# pc_max30003_brk_v2_0.net
KiCad netlist of a schematic drawn in EAGLE
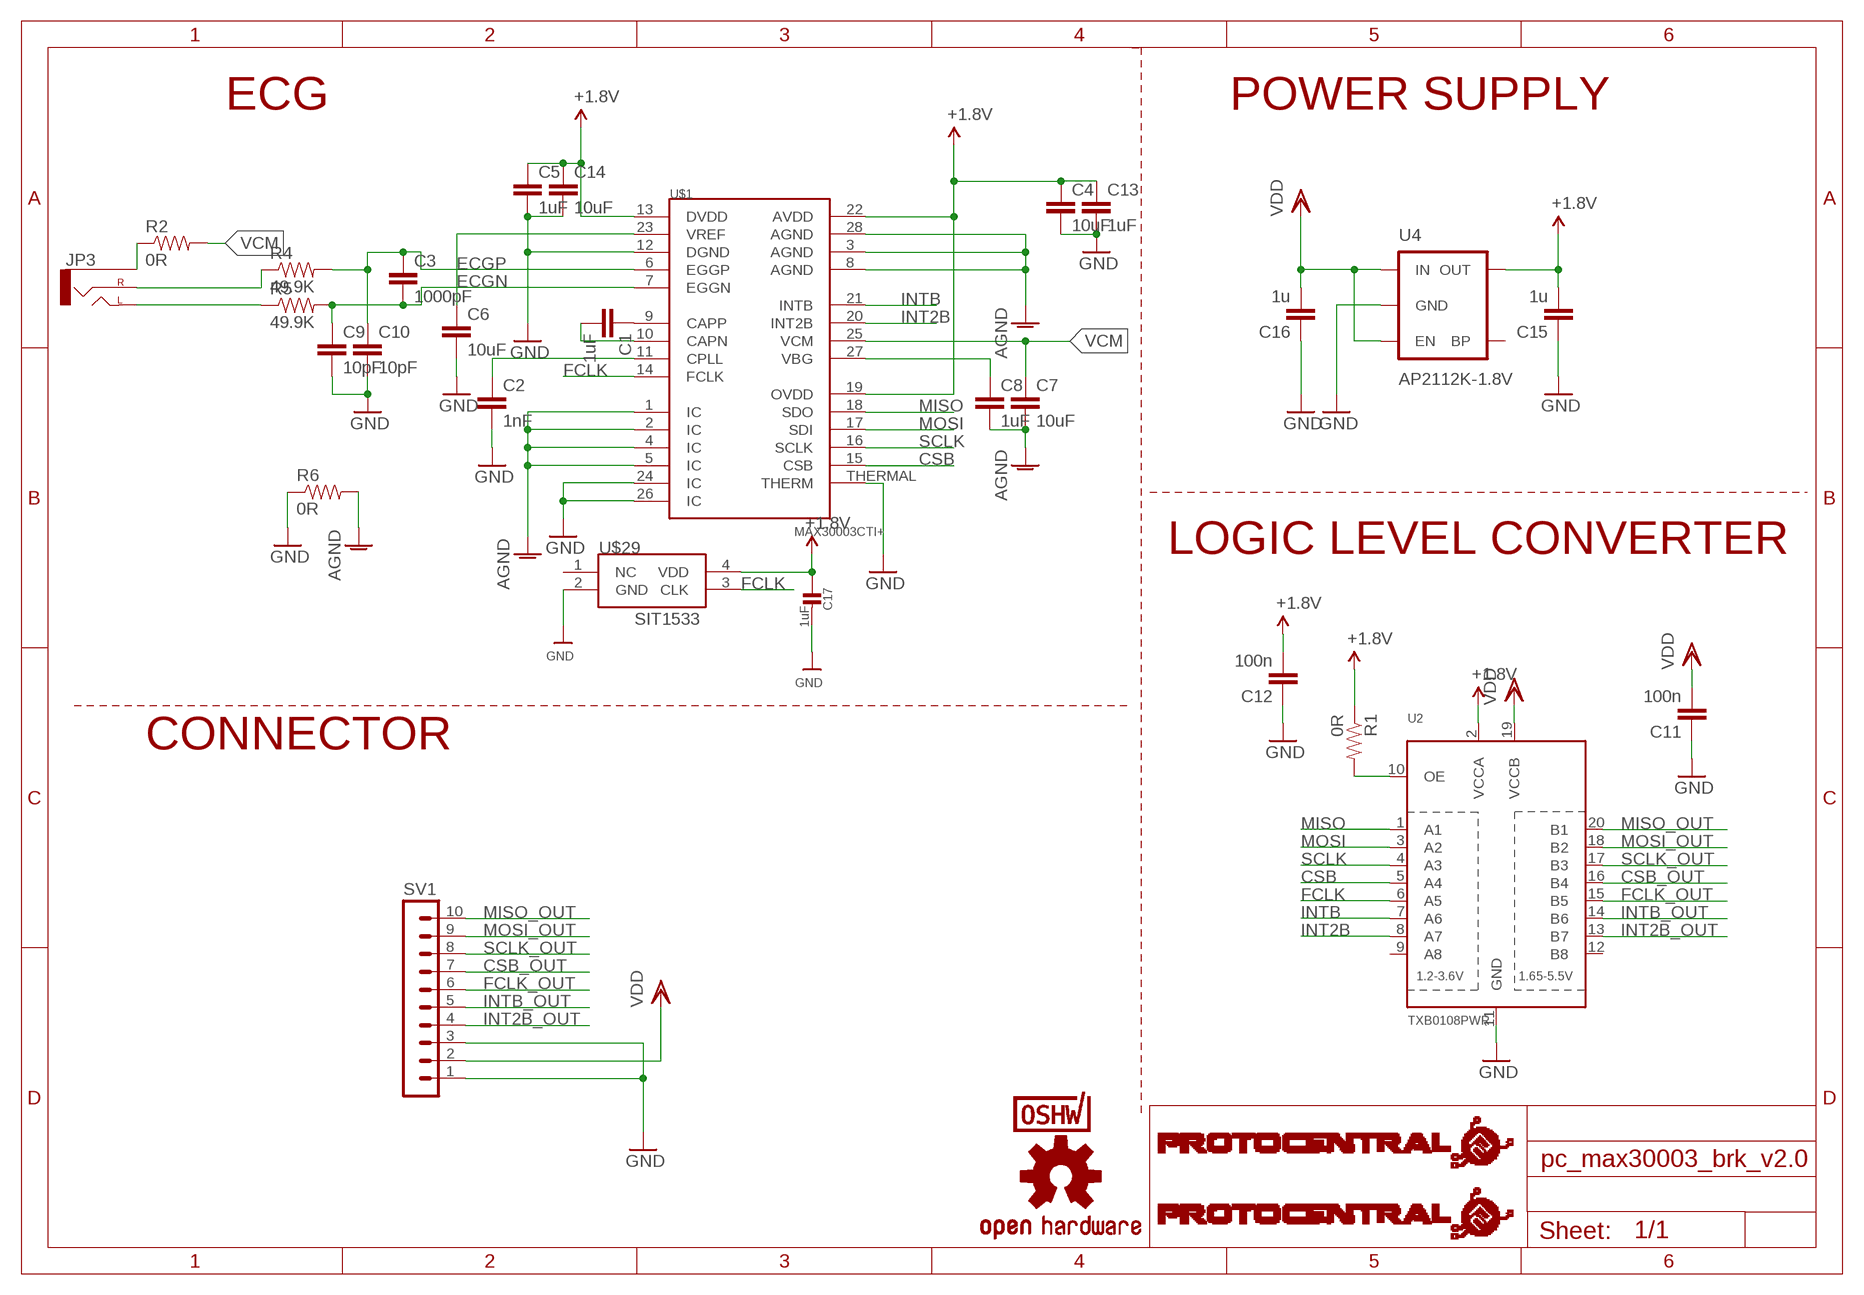
[diagram p0: schematic, sheet 1]

(export (version "E")
  (design (tool "Eeschema 10.0.6"))
  (components
    (comp (ref "C1")
      (value "1uF")
      (footprint "eagle-import:C0805")
      (libsource (lib "eagle-import") (part "C-EUC0805"))
    )
    (comp (ref "C2")
      (value "1nF")
      (footprint "eagle-import:C0805")
      (libsource (lib "eagle-import") (part "C-EUC0805"))
    )
    (comp (ref "C3")
      (value "1000pF")
      (footprint "eagle-import:C0402")
      (libsource (lib "eagle-import") (part "C-EUC0402"))
    )
    (comp (ref "C4")
      (value "10uF")
      (footprint "eagle-import:C0805")
      (libsource (lib "eagle-import") (part "C-EUC0805"))
    )
    (comp (ref "C5")
      (value "1uF")
      (footprint "eagle-import:C0805")
      (libsource (lib "eagle-import") (part "C-EUC0805"))
    )
    (comp (ref "C6")
      (value "10uF")
      (footprint "eagle-import:C0805")
      (libsource (lib "eagle-import") (part "C-EUC0805"))
    )
    (comp (ref "C7")
      (value "10uF")
      (footprint "eagle-import:C0805")
      (libsource (lib "eagle-import") (part "C-EUC0805"))
    )
    (comp (ref "C8")
      (value "1uF")
      (footprint "eagle-import:C0805")
      (libsource (lib "eagle-import") (part "C-EUC0805"))
    )
    (comp (ref "C9")
      (value "10pF")
      (footprint "eagle-import:C0402")
      (libsource (lib "eagle-import") (part "C-EUC0402"))
    )
    (comp (ref "C10")
      (value "10pF")
      (footprint "eagle-import:C0402")
      (libsource (lib "eagle-import") (part "C-EUC0402"))
    )
    (comp (ref "C11")
      (value "100n")
      (footprint "eagle-import:C0402")
      (libsource (lib "eagle-import") (part "C-EUC0402"))
    )
    (comp (ref "C12")
      (value "100n")
      (footprint "eagle-import:C0402")
      (libsource (lib "eagle-import") (part "C-EUC0402"))
    )
    (comp (ref "C13")
      (value "1uF")
      (footprint "eagle-import:C0805")
      (libsource (lib "eagle-import") (part "C-EUC0805"))
    )
    (comp (ref "C14")
      (value "10uF")
      (footprint "eagle-import:C0805")
      (libsource (lib "eagle-import") (part "C-EUC0805"))
    )
    (comp (ref "C15")
      (value "1u")
      (footprint "eagle-import:C0805")
      (libsource (lib "eagle-import") (part "C-EUC0805"))
    )
    (comp (ref "C16")
      (value "1u")
      (footprint "eagle-import:C0805")
      (libsource (lib "eagle-import") (part "C-EUC0805"))
    )
    (comp (ref "C17")
      (value "1uF")
      (footprint "eagle-import:_0402")
      (libsource (lib "eagle-import") (part "CAP_CERAMIC_0402"))
    )
    (comp (ref "JP3")
      (value "AUDIO-JACKSMD2")
      (footprint "eagle-import:AUDIO-JACK-3.5MM-SMD")
      (libsource (lib "eagle-import") (part "AUDIO-JACKSMD2"))
    )
    (comp (ref "R1")
      (value "0R")
      (footprint "eagle-import:0805")
      (libsource (lib "eagle-import") (part "RESISTOR0805-RES"))
    )
    (comp (ref "R2")
      (value "0R")
      (footprint "eagle-import:0805")
      (libsource (lib "eagle-import") (part "RESISTOR0805-RES"))
    )
    (comp (ref "R4")
      (value "49.9K")
      (footprint "eagle-import:0805")
      (libsource (lib "eagle-import") (part "RESISTOR0805-RES"))
    )
    (comp (ref "R5")
      (value "49.9K")
      (footprint "eagle-import:0805")
      (libsource (lib "eagle-import") (part "RESISTOR0805-RES"))
    )
    (comp (ref "R6")
      (value "0R")
      (footprint "eagle-import:0805")
      (libsource (lib "eagle-import") (part "RESISTOR0805-RES"))
    )
    (comp (ref "SV1")
      (value "MA10-1")
      (footprint "eagle-import:MA10-1")
      (libsource (lib "eagle-import") (part "MA10-1"))
    )
    (comp (ref "U$1")
      (value "MAX30003CTI+")
      (footprint "eagle-import:QFN-28")
      (libsource (lib "eagle-import") (part "MAX30003"))
    )
    (comp (ref "U$2")
      (value "PROTY_LOGO_WITH_TEXT")
      (footprint "eagle-import:PROTY_WITH_TEXT")
      (libsource (lib "eagle-import") (part "PROTY_LOGO_WITH_TEXT"))
    )
    (comp (ref "U$3")
      (value "PROTY-LOGO")
      (footprint "eagle-import:LOGO-PROTY")
      (libsource (lib "eagle-import") (part "PROTY-LOGO"))
    )
    (comp (ref "U$6")
      (value "OSHW-LOGOS")
      (footprint "eagle-import:OSHW-LOGO-S")
      (libsource (lib "eagle-import") (part "OSHW-LOGOS"))
    )
    (comp (ref "U$7")
      (value "CERT-SMALL")
      (footprint "eagle-import:CERT-SMALL-SILK")
      (libsource (lib "eagle-import") (part "CERT-SMALL"))
    )
    (comp (ref "U$29")
      (value "SIT1533")
      (footprint "eagle-import:SIT1533")
      (libsource (lib "eagle-import") (part "SIT1533"))
    )
    (comp (ref "U2")
      (value "TXB0108PWR")
      (footprint "eagle-import:TSSOP20")
      (libsource (lib "eagle-import") (part "TXB0108PWR"))
    )
    (comp (ref "U4")
      (value "AP2112K-1.8V")
      (footprint "eagle-import:SOT23-5")
      (libsource (lib "eagle-import") (part "V_REG_LDOSMD"))
    )
  )
  (nets
    (net (code "1") (name "+1.8V") (class "Default")
      (node (ref "C12") (pin "2") (pinfunction "2_2") (pintype "passive"))
      (node (ref "C13") (pin "1") (pinfunction "1_1") (pintype "passive"))
      (node (ref "C14") (pin "1") (pinfunction "1_1") (pintype "passive"))
      (node (ref "C15") (pin "2") (pinfunction "2_2") (pintype "passive"))
      (node (ref "C17") (pin "1") (pinfunction "1_1") (pintype "passive"))
      (node (ref "C4") (pin "1") (pinfunction "1_1") (pintype "passive"))
      (node (ref "C5") (pin "1") (pinfunction "1_1") (pintype "passive"))
      (node (ref "R1") (pin "1") (pinfunction "1_1") (pintype "passive"))
      (node (ref "U$1") (pin "13") (pinfunction "DVDD_13") (pintype "bidirectional"))
      (node (ref "U$1") (pin "19") (pinfunction "OVDD_19") (pintype "bidirectional"))
      (node (ref "U$1") (pin "22") (pinfunction "AVDD_22") (pintype "bidirectional"))
      (node (ref "U$29") (pin "4") (pinfunction "VDD_4") (pintype "bidirectional"))
      (node (ref "U2") (pin "2") (pinfunction "VCCA_2") (pintype "bidirectional"))
      (node (ref "U4") (pin "5") (pinfunction "OUT_5") (pintype "passive"))
    )
    (net (code "2") (name "/CSB") (class "Default")
      (node (ref "U$1") (pin "15") (pinfunction "CSB_15") (pintype "bidirectional"))
      (node (ref "U2") (pin "5") (pinfunction "A4_5") (pintype "bidirectional"))
    )
    (net (code "3") (name "/CSB_OUT") (class "Default")
      (node (ref "SV1") (pin "7") (pinfunction "7_7") (pintype "passive"))
      (node (ref "U2") (pin "16") (pinfunction "B4_16") (pintype "bidirectional"))
    )
    (net (code "4") (name "/ECGN") (class "Default")
      (node (ref "C3") (pin "2") (pinfunction "2_2") (pintype "passive"))
      (node (ref "C9") (pin "1") (pinfunction "1_1") (pintype "passive"))
      (node (ref "R5") (pin "2") (pinfunction "2_2") (pintype "passive"))
      (node (ref "U$1") (pin "7") (pinfunction "EGGN_7") (pintype "bidirectional"))
    )
    (net (code "5") (name "/ECGP") (class "Default")
      (node (ref "C10") (pin "1") (pinfunction "1_1") (pintype "passive"))
      (node (ref "C3") (pin "1") (pinfunction "1_1") (pintype "passive"))
      (node (ref "R4") (pin "2") (pinfunction "2_2") (pintype "passive"))
      (node (ref "U$1") (pin "6") (pinfunction "EGGP_6") (pintype "bidirectional"))
    )
    (net (code "6") (name "/FCLK") (class "Default")
      (node (ref "U$1") (pin "14") (pinfunction "FCLK_14") (pintype "bidirectional"))
      (node (ref "U$29") (pin "3") (pinfunction "CLK_3") (pintype "bidirectional"))
      (node (ref "U2") (pin "6") (pinfunction "A5_6") (pintype "bidirectional"))
    )
    (net (code "7") (name "/FCLK_OUT") (class "Default")
      (node (ref "SV1") (pin "6") (pinfunction "6_6") (pintype "passive"))
      (node (ref "U2") (pin "15") (pinfunction "B5_15") (pintype "bidirectional"))
    )
    (net (code "8") (name "/INT2B") (class "Default")
      (node (ref "U$1") (pin "20") (pinfunction "INT2B_20") (pintype "bidirectional"))
      (node (ref "U2") (pin "8") (pinfunction "A7_8") (pintype "bidirectional"))
    )
    (net (code "9") (name "/INT2B_OUT") (class "Default")
      (node (ref "SV1") (pin "4") (pinfunction "4_4") (pintype "passive"))
      (node (ref "U2") (pin "13") (pinfunction "B7_13") (pintype "bidirectional"))
    )
    (net (code "10") (name "/INTB") (class "Default")
      (node (ref "U$1") (pin "21") (pinfunction "INTB_21") (pintype "bidirectional"))
      (node (ref "U2") (pin "7") (pinfunction "A6_7") (pintype "bidirectional"))
    )
    (net (code "11") (name "/INTB_OUT") (class "Default")
      (node (ref "SV1") (pin "5") (pinfunction "5_5") (pintype "passive"))
      (node (ref "U2") (pin "14") (pinfunction "B6_14") (pintype "bidirectional"))
    )
    (net (code "12") (name "/MISO") (class "Default")
      (node (ref "U$1") (pin "18") (pinfunction "SDO_18") (pintype "bidirectional"))
      (node (ref "U2") (pin "1") (pinfunction "A1_1") (pintype "bidirectional"))
    )
    (net (code "13") (name "/MISO_OUT") (class "Default")
      (node (ref "SV1") (pin "10") (pinfunction "10_10") (pintype "passive"))
      (node (ref "U2") (pin "20") (pinfunction "B1_20") (pintype "bidirectional"))
    )
    (net (code "14") (name "/MOSI") (class "Default")
      (node (ref "U$1") (pin "17") (pinfunction "SDI_17") (pintype "bidirectional"))
      (node (ref "U2") (pin "3") (pinfunction "A2_3") (pintype "bidirectional"))
    )
    (net (code "15") (name "/MOSI_OUT") (class "Default")
      (node (ref "SV1") (pin "9") (pinfunction "9_9") (pintype "passive"))
      (node (ref "U2") (pin "18") (pinfunction "B2_18") (pintype "bidirectional"))
    )
    (net (code "16") (name "/SCLK") (class "Default")
      (node (ref "U$1") (pin "16") (pinfunction "SCLK_16") (pintype "bidirectional"))
      (node (ref "U2") (pin "4") (pinfunction "A3_4") (pintype "bidirectional"))
    )
    (net (code "17") (name "/SCLK_OUT") (class "Default")
      (node (ref "SV1") (pin "8") (pinfunction "8_8") (pintype "passive"))
      (node (ref "U2") (pin "17") (pinfunction "B3_17") (pintype "bidirectional"))
    )
    (net (code "18") (name "AGND") (class "Default")
      (node (ref "C7") (pin "2") (pinfunction "2_2") (pintype "passive"))
      (node (ref "C8") (pin "2") (pinfunction "2_2") (pintype "passive"))
      (node (ref "R6") (pin "2") (pinfunction "2_2") (pintype "passive"))
      (node (ref "U$1") (pin "1") (pinfunction "IC_1") (pintype "bidirectional"))
      (node (ref "U$1") (pin "2") (pinfunction "IC_2") (pintype "bidirectional"))
      (node (ref "U$1") (pin "28") (pinfunction "AGND_28") (pintype "bidirectional"))
      (node (ref "U$1") (pin "3") (pinfunction "AGND_3") (pintype "bidirectional"))
      (node (ref "U$1") (pin "4") (pinfunction "IC_4") (pintype "bidirectional"))
      (node (ref "U$1") (pin "5") (pinfunction "IC_5") (pintype "bidirectional"))
      (node (ref "U$1") (pin "8") (pinfunction "AGND_8") (pintype "bidirectional"))
    )
    (net (code "19") (name "GND") (class "Default")
      (node (ref "C10") (pin "2") (pinfunction "2_2") (pintype "passive"))
      (node (ref "C11") (pin "1") (pinfunction "1_1") (pintype "passive"))
      (node (ref "C12") (pin "1") (pinfunction "1_1") (pintype "passive"))
      (node (ref "C13") (pin "2") (pinfunction "2_2") (pintype "passive"))
      (node (ref "C14") (pin "2") (pinfunction "2_2") (pintype "passive"))
      (node (ref "C15") (pin "1") (pinfunction "1_1") (pintype "passive"))
      (node (ref "C16") (pin "1") (pinfunction "1_1") (pintype "passive"))
      (node (ref "C17") (pin "2") (pinfunction "2_2") (pintype "passive"))
      (node (ref "C2") (pin "2") (pinfunction "2_2") (pintype "passive"))
      (node (ref "C4") (pin "2") (pinfunction "2_2") (pintype "passive"))
      (node (ref "C5") (pin "2") (pinfunction "2_2") (pintype "passive"))
      (node (ref "C6") (pin "2") (pinfunction "2_2") (pintype "passive"))
      (node (ref "C9") (pin "2") (pinfunction "2_2") (pintype "passive"))
      (node (ref "R6") (pin "1") (pinfunction "1_1") (pintype "passive"))
      (node (ref "SV1") (pin "1") (pinfunction "1_1") (pintype "passive"))
      (node (ref "SV1") (pin "3") (pinfunction "3_3") (pintype "passive"))
      (node (ref "U$1") (pin "12") (pinfunction "DGND_12") (pintype "bidirectional"))
      (node (ref "U$1") (pin "24") (pinfunction "IC_24") (pintype "bidirectional"))
      (node (ref "U$1") (pin "26") (pinfunction "IC_26") (pintype "bidirectional"))
      (node (ref "U$1") (pin "THERMAL") (pinfunction "THERM_THERMAL") (pintype "bidirectional"))
      (node (ref "U$29") (pin "2") (pinfunction "GND_2") (pintype "bidirectional"))
      (node (ref "U2") (pin "11") (pinfunction "GND_11") (pintype "bidirectional"))
      (node (ref "U4") (pin "2") (pinfunction "GND_2") (pintype "input"))
    )
    (net (code "20") (name "Net-(JP3-LEFT)") (class "Default")
      (node (ref "JP3") (pin "TIP") (pinfunction "LEFT_TIP") (pintype "bidirectional"))
      (node (ref "R5") (pin "1") (pinfunction "1_1") (pintype "passive"))
    )
    (net (code "21") (name "Net-(JP3-PadSLEEVE)") (class "Default")
      (node (ref "JP3") (pin "SLEEVE") (pinfunction "SLEEVE_SLEEVE") (pintype "bidirectional"))
      (node (ref "R2") (pin "1") (pinfunction "1_1") (pintype "passive"))
    )
    (net (code "22") (name "Net-(JP3-RIGHT)") (class "Default")
      (node (ref "JP3") (pin "RING") (pinfunction "RIGHT_RING") (pintype "bidirectional"))
      (node (ref "R4") (pin "1") (pinfunction "1_1") (pintype "passive"))
    )
    (net (code "23") (name "Net-(U$1-CAPN)") (class "Default")
      (node (ref "C1") (pin "2") (pinfunction "2_2") (pintype "passive"))
      (node (ref "U$1") (pin "10") (pinfunction "CAPN_10") (pintype "bidirectional"))
    )
    (net (code "24") (name "Net-(U$1-CAPP)") (class "Default")
      (node (ref "C1") (pin "1") (pinfunction "1_1") (pintype "passive"))
      (node (ref "U$1") (pin "9") (pinfunction "CAPP_9") (pintype "bidirectional"))
    )
    (net (code "25") (name "Net-(U$1-CPLL)") (class "Default")
      (node (ref "C2") (pin "1") (pinfunction "1_1") (pintype "passive"))
      (node (ref "U$1") (pin "11") (pinfunction "CPLL_11") (pintype "bidirectional"))
    )
    (net (code "26") (name "Net-(U$1-VBG)") (class "Default")
      (node (ref "C8") (pin "1") (pinfunction "1_1") (pintype "passive"))
      (node (ref "U$1") (pin "27") (pinfunction "VBG_27") (pintype "bidirectional"))
    )
    (net (code "27") (name "Net-(U$1-VREF)") (class "Default")
      (node (ref "C6") (pin "1") (pinfunction "1_1") (pintype "passive"))
      (node (ref "U$1") (pin "23") (pinfunction "VREF_23") (pintype "bidirectional"))
    )
    (net (code "28") (name "Net-(U2-OE)") (class "Default")
      (node (ref "R1") (pin "2") (pinfunction "2_2") (pintype "passive"))
      (node (ref "U2") (pin "10") (pinfunction "OE_10") (pintype "bidirectional"))
    )
    (net (code "29") (name "VCM") (class "Default")
      (node (ref "C7") (pin "1") (pinfunction "1_1") (pintype "passive"))
      (node (ref "R2") (pin "2") (pinfunction "2_2") (pintype "passive"))
      (node (ref "U$1") (pin "25") (pinfunction "VCM_25") (pintype "bidirectional"))
    )
    (net (code "30") (name "VDD") (class "Default")
      (node (ref "C11") (pin "2") (pinfunction "2_2") (pintype "passive"))
      (node (ref "C16") (pin "2") (pinfunction "2_2") (pintype "passive"))
      (node (ref "SV1") (pin "2") (pinfunction "2_2") (pintype "passive"))
      (node (ref "U2") (pin "19") (pinfunction "VCCB_19") (pintype "bidirectional"))
      (node (ref "U4") (pin "1") (pinfunction "IN_1") (pintype "input"))
      (node (ref "U4") (pin "3") (pinfunction "EN_3") (pintype "input"))
    )
    (net (code "31") (name "unconnected-(U$29-NC-Pad1)") (class "Default")
      (node (ref "U$29") (pin "1") (pinfunction "NC_1") (pintype "bidirectional"))
    )
    (net (code "32") (name "unconnected-(U2-A8-Pad9)") (class "Default")
      (node (ref "U2") (pin "9") (pinfunction "A8_9") (pintype "bidirectional"))
    )
    (net (code "33") (name "unconnected-(U2-B8-Pad12)") (class "Default")
      (node (ref "U2") (pin "12") (pinfunction "B8_12") (pintype "bidirectional"))
    )
    (net (code "34") (name "unconnected-(U4-BP-Pad4)") (class "Default")
      (node (ref "U4") (pin "4") (pinfunction "BP_4") (pintype "input"))
    )
  )
)
